# LNA.net
KiCad netlist of a schematic drawn in Altium Designer
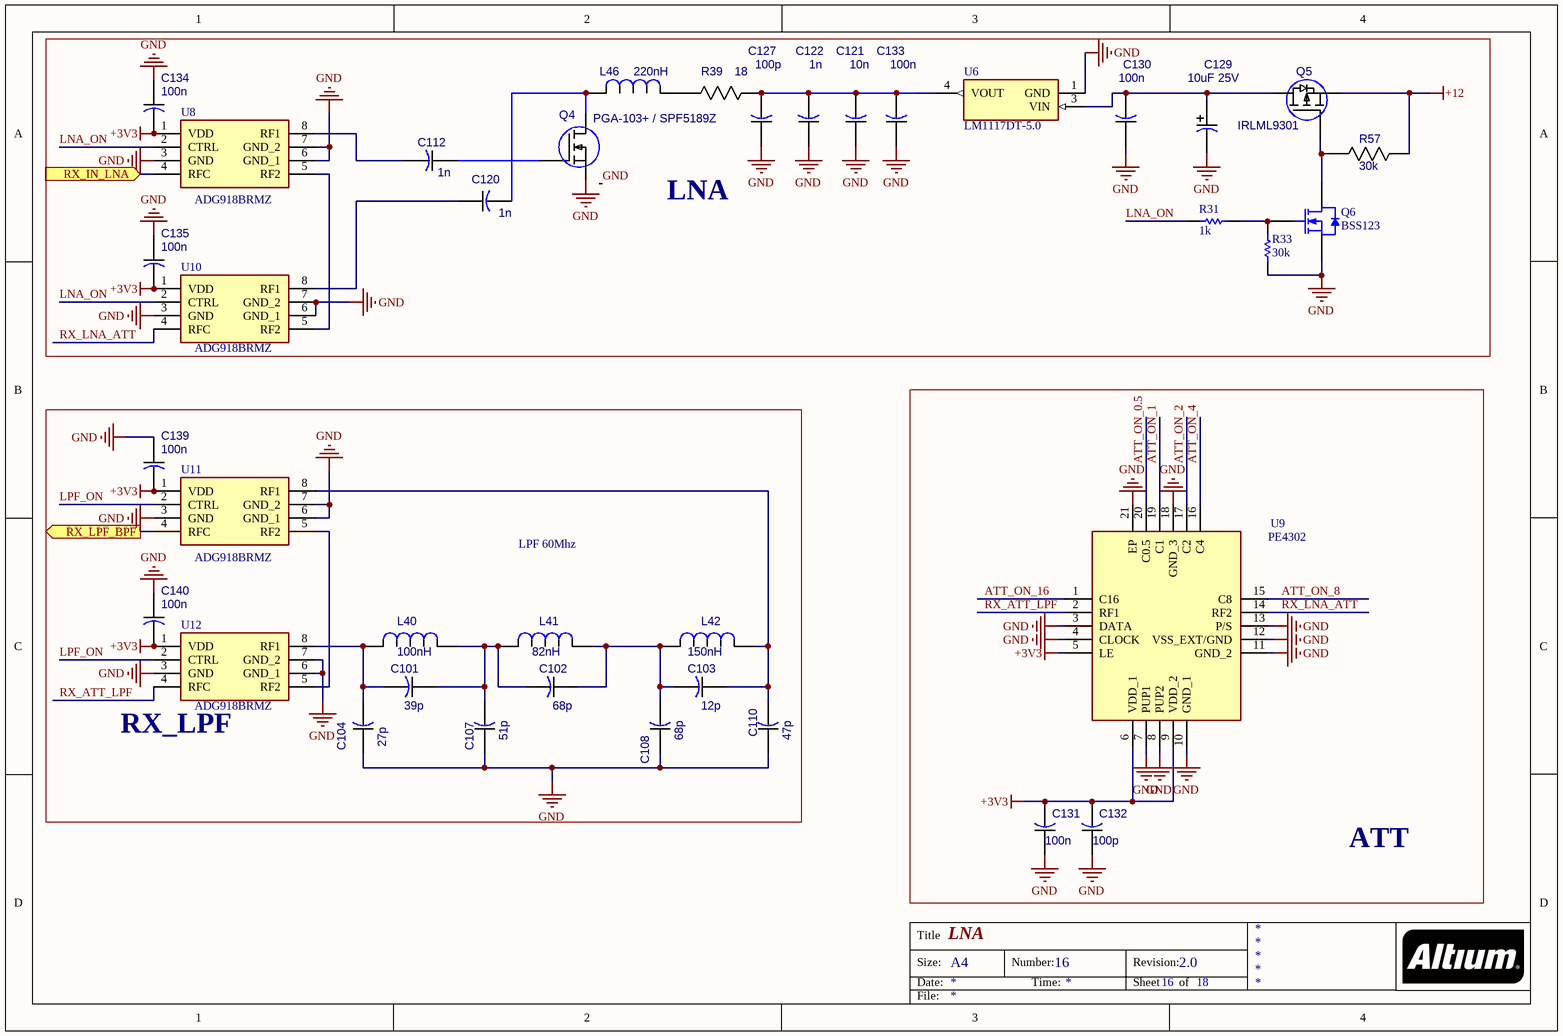
[diagram p0: LNA.SchDoc]

(export (version "E")
  (design (tool "Eeschema 10.0.6"))
  (components
    (comp (ref "C101")
      (value "39p")
      (footprint "CAP_0805")
      (description "CAP_0805")
      (libsource (lib "*") (part "CAP_0805"))
    )
    (comp (ref "C102")
      (value "68p")
      (footprint "CAP_0805")
      (description "CAP_0805")
      (libsource (lib "*") (part "CAP_0805"))
    )
    (comp (ref "C103")
      (value "12p")
      (footprint "CAP_0805")
      (description "CAP_0805")
      (libsource (lib "*") (part "CAP_0805"))
    )
    (comp (ref "C104")
      (value "27p")
      (footprint "CAP_0805")
      (description "CAP_0805")
      (libsource (lib "*") (part "CAP_0805"))
    )
    (comp (ref "C107")
      (value "51p")
      (footprint "CAP_0805")
      (description "CAP_0805")
      (libsource (lib "*") (part "CAP_0805"))
    )
    (comp (ref "C108")
      (value "68p")
      (footprint "CAP_0805")
      (description "CAP_0805")
      (libsource (lib "*") (part "CAP_0805"))
    )
    (comp (ref "C110")
      (value "47p")
      (footprint "CAP_0805")
      (description "CAP_0805")
      (libsource (lib "*") (part "CAP_0805"))
    )
    (comp (ref "C112")
      (value "1n")
      (footprint "CAP_0805")
      (description "CAP_0805")
      (libsource (lib "*") (part "CAP_0805"))
    )
    (comp (ref "C120")
      (value "1n")
      (footprint "CAP_0805")
      (description "CAP_0805")
      (libsource (lib "*") (part "CAP_0805"))
    )
    (comp (ref "C121")
      (value "10n")
      (footprint "6-0805_M")
      (description "CAP_0805")
      (libsource (lib "*") (part "CAP_0805"))
    )
    (comp (ref "C122")
      (value "1n")
      (footprint "6-0805_M")
      (description "CAP_0805")
      (libsource (lib "*") (part "CAP_0805"))
    )
    (comp (ref "C127")
      (value "100p")
      (footprint "6-0805_M")
      (description "CAP_0805")
      (libsource (lib "*") (part "CAP_0805"))
    )
    (comp (ref "C129")
      (value "10uF 25V")
      (footprint "CAPAE_5.3x5.3h6.1")
      (description "CAPAE_5.3x5.3h6.1")
      (libsource (lib "*") (part "CAPAE_5.3x5.3h6.1"))
    )
    (comp (ref "C130")
      (value "100n")
      (footprint "CAP_0805")
      (description "CAP_0805")
      (libsource (lib "") (part "CAP_0805_1"))
    )
    (comp (ref "C131")
      (value "100n")
      (footprint "6-0805_M")
      (description "CAP_0805")
      (libsource (lib "*") (part "CAP_0805"))
    )
    (comp (ref "C132")
      (value "100p")
      (footprint "6-0805_M")
      (description "CAP_0805")
      (libsource (lib "*") (part "CAP_0805"))
    )
    (comp (ref "C133")
      (value "100n")
      (footprint "CAP_0805")
      (description "CAP_0805")
      (libsource (lib "*") (part "CAP_0805"))
    )
    (comp (ref "C134")
      (value "100n")
      (footprint "CAP_0805")
      (description "CAP_0805")
      (libsource (lib "*") (part "CAP_0805"))
    )
    (comp (ref "C135")
      (value "100n")
      (footprint "CAP_0805")
      (description "CAP_0805")
      (libsource (lib "*") (part "CAP_0805"))
    )
    (comp (ref "C139")
      (value "100n")
      (footprint "CAP_0805")
      (description "CAP_0805")
      (libsource (lib "*") (part "CAP_0805"))
    )
    (comp (ref "C140")
      (value "100n")
      (footprint "CAP_0805")
      (description "CAP_0805")
      (libsource (lib "*") (part "CAP_0805"))
    )
    (comp (ref "L40")
      (value "100nH")
      (footprint "IND_0805")
      (description "IND_0805")
      (libsource (lib "*") (part "IND_0805"))
    )
    (comp (ref "L41")
      (value "82nH")
      (footprint "IND_0805")
      (description "IND_0805")
      (libsource (lib "*") (part "IND_0805"))
    )
    (comp (ref "L42")
      (value "150nH")
      (footprint "IND_0805")
      (description "IND_0805")
      (libsource (lib "*") (part "IND_0805"))
    )
    (comp (ref "L46")
      (value "220nH")
      (footprint "IND_1206")
      (description "IND_1206")
      (libsource (lib "*") (part "IND_1206"))
    )
    (comp (ref "Q4")
      (value "PGA-103+ / SPF5189Z")
      (footprint "SOT89")
      (libsource (lib "*") (part "PGA-103+"))
    )
    (comp (ref "Q5")
      (value "IRLML9301")
      (footprint "SOT23")
      (description "MOSFET")
      (libsource (lib "*") (part "MOSFET_ENH_PD"))
    )
    (comp (ref "Q6")
      (value "BSS123")
      (footprint "FAIR-SOT23-3_V")
      (fields (field (name "MANUFACTURER") "Fairchild"))
      (libsource (lib "Altium Content Vault") (part "NEMOS-GSD-3"))
    )
    (comp (ref "R31")
      (value "1k")
      (footprint "RESC2013X60X40NL20T25")
      (description "RES_0805")
      (fields (field (name "MANUFACTURER") "Panasonic") (field (name "PART NUMBER") "ERA-6AEB303V"))
      (libsource (lib "Altium Content Vault") (part "RES"))
    )
    (comp (ref "R33")
      (value "30k")
      (footprint "RESC2013X60X40NL20T25")
      (description "RES_0805")
      (fields (field (name "MANUFACTURER") "Panasonic") (field (name "PART NUMBER") "ERA-6AEB303V"))
      (libsource (lib "Altium Content Vault") (part "RES"))
    )
    (comp (ref "R39")
      (value "18")
      (footprint "RES_1206")
      (description "RES_1206")
      (libsource (lib "*") (part "RES_1206"))
    )
    (comp (ref "R57")
      (value "30k")
      (footprint "RES_0805")
      (description "RES_0805")
      (libsource (lib "*") (part "RES_0805"))
    )
    (comp (ref "U6")
      (value "LM1117DT-5.0")
      (footprint "SamacSys:TO228P991X238-3N")
      (description "Integrated Circuit")
      (fields
        (field (name "MANUFACTURER_PART_NUMBER") "LM1117DT-ADJ")
        (field (name "MOUSER PART NUMBER") "926-LM1117DT-ADJ")
      )
      (libsource (lib "*") (part "LM1117DT-ADJ"))
    )
    (comp (ref "U8")
      (value "ADG918BRMZ")
      (footprint "SamacSys:SOP65P490X110-8N")
      (description "Integrated Circuit")
      (fields (field (name "MOUSER PART NUMBER") "584-ADG918BRMZ") (field (name "RS PART NUMBER") "4969212P"))
      (libsource (lib "*") (part "ADG918BRMZ"))
    )
    (comp (ref "U9")
      (value "PE4302")
      (footprint "SamacSys:QFN50P400X400X90-21N")
      (description "Integrated Circuit")
      (fields (field (name "MANUFACTURER_PART_NUMBER") "PE4312C-Z"))
      (libsource (lib "*") (part "PE4312C-Z"))
    )
    (comp (ref "U10")
      (value "ADG918BRMZ")
      (footprint "SamacSys:SOP65P490X110-8N")
      (description "Integrated Circuit")
      (fields (field (name "MOUSER PART NUMBER") "584-ADG918BRMZ") (field (name "RS PART NUMBER") "4969212P"))
      (libsource (lib "*") (part "ADG918BRMZ"))
    )
    (comp (ref "U11")
      (value "ADG918BRMZ")
      (footprint "SamacSys:SOP65P490X110-8N")
      (description "Integrated Circuit")
      (fields (field (name "MOUSER PART NUMBER") "584-ADG918BRMZ") (field (name "RS PART NUMBER") "4969212P"))
      (libsource (lib "*") (part "ADG918BRMZ"))
    )
    (comp (ref "U12")
      (value "ADG918BRMZ")
      (footprint "SamacSys:SOP65P490X110-8N")
      (description "Integrated Circuit")
      (fields (field (name "MOUSER PART NUMBER") "584-ADG918BRMZ") (field (name "RS PART NUMBER") "4969212P"))
      (libsource (lib "*") (part "ADG918BRMZ"))
    )
  )
  (nets
    (net (code "1") (name "+3V3") (class "Default")
      (node (ref "C131") (pin "2") (pinfunction "2_2") (pintype "passive"))
      (node (ref "C132") (pin "2") (pinfunction "2_2") (pintype "passive"))
      (node (ref "C134") (pin "2") (pinfunction "2_2") (pintype "passive"))
      (node (ref "C135") (pin "2") (pinfunction "2_2") (pintype "passive"))
      (node (ref "C139") (pin "2") (pinfunction "2_2") (pintype "passive"))
      (node (ref "C140") (pin "2") (pinfunction "2_2") (pintype "passive"))
      (node (ref "U10") (pin "1") (pinfunction "VDD_1") (pintype "power_in"))
      (node (ref "U11") (pin "1") (pinfunction "VDD_1") (pintype "power_in"))
      (node (ref "U12") (pin "1") (pinfunction "VDD_1") (pintype "power_in"))
      (node (ref "U8") (pin "1") (pinfunction "VDD_1") (pintype "power_in"))
      (node (ref "U9") (pin "5") (pinfunction "LE_5") (pintype "passive"))
      (node (ref "U9") (pin "6") (pinfunction "VDD_1_6") (pintype "passive"))
      (node (ref "U9") (pin "9") (pinfunction "VDD_2_9") (pintype "passive"))
    )
    (net (code "2") (name "+12") (class "Default")
      (node (ref "Q5") (pin "2") (pinfunction "S_2") (pintype "passive"))
      (node (ref "R57") (pin "2") (pinfunction "2_2") (pintype "passive"))
    )
    (net (code "3") (name "/ATT_ON_0.5") (class "Default")
      (node (ref "U9") (pin "20") (pinfunction "C0.5_20") (pintype "passive"))
    )
    (net (code "4") (name "/ATT_ON_1") (class "Default")
      (node (ref "U9") (pin "19") (pinfunction "C1_19") (pintype "passive"))
    )
    (net (code "5") (name "/ATT_ON_2") (class "Default")
      (node (ref "U9") (pin "17") (pinfunction "C2_17") (pintype "passive"))
    )
    (net (code "6") (name "/ATT_ON_4") (class "Default")
      (node (ref "U9") (pin "16") (pinfunction "C4_16") (pintype "passive"))
    )
    (net (code "7") (name "/ATT_ON_8") (class "Default")
      (node (ref "U9") (pin "15") (pinfunction "C8_15") (pintype "passive"))
    )
    (net (code "8") (name "/ATT_ON_16") (class "Default")
      (node (ref "U9") (pin "1") (pinfunction "C16_1") (pintype "passive"))
    )
    (net (code "9") (name "/LNA_ON") (class "Default")
      (node (ref "R31") (pin "2") (pinfunction "2_2") (pintype "passive"))
      (node (ref "U10") (pin "2") (pinfunction "CTRL_2") (pintype "passive"))
      (node (ref "U8") (pin "2") (pinfunction "CTRL_2") (pintype "passive"))
    )
    (net (code "10") (name "/LPF_ON") (class "Default")
      (node (ref "U11") (pin "2") (pinfunction "CTRL_2") (pintype "passive"))
      (node (ref "U12") (pin "2") (pinfunction "CTRL_2") (pintype "passive"))
    )
    (net (code "11") (name "/RX_ATT_LPF") (class "Default")
      (node (ref "U12") (pin "4") (pinfunction "RFC_4") (pintype "passive"))
      (node (ref "U9") (pin "2") (pinfunction "RF1_2") (pintype "passive"))
    )
    (net (code "12") (name "/RX_IN_LNA") (class "Default")
      (node (ref "U8") (pin "4") (pinfunction "RFC_4") (pintype "passive"))
    )
    (net (code "13") (name "/RX_LNA_ATT") (class "Default")
      (node (ref "U10") (pin "4") (pinfunction "RFC_4") (pintype "passive"))
      (node (ref "U9") (pin "14") (pinfunction "RF2_14") (pintype "passive"))
    )
    (net (code "14") (name "/RX_LPF_BPF") (class "Default")
      (node (ref "U11") (pin "4") (pinfunction "RFC_4") (pintype "passive"))
    )
    (net (code "15") (name "GND") (class "Default")
      (node (ref "C104") (pin "1") (pinfunction "1_1") (pintype "passive"))
      (node (ref "C107") (pin "1") (pinfunction "1_1") (pintype "passive"))
      (node (ref "C108") (pin "1") (pinfunction "1_1") (pintype "passive"))
      (node (ref "C110") (pin "1") (pinfunction "1_1") (pintype "passive"))
      (node (ref "C121") (pin "1") (pinfunction "1_1") (pintype "passive"))
      (node (ref "C122") (pin "1") (pinfunction "1_1") (pintype "passive"))
      (node (ref "C127") (pin "1") (pinfunction "1_1") (pintype "passive"))
      (node (ref "C129") (pin "2") (pinfunction "MINUS_2") (pintype "passive"))
      (node (ref "C130") (pin "1") (pinfunction "1_1") (pintype "passive"))
      (node (ref "C131") (pin "1") (pinfunction "1_1") (pintype "passive"))
      (node (ref "C132") (pin "1") (pinfunction "1_1") (pintype "passive"))
      (node (ref "C133") (pin "1") (pinfunction "1_1") (pintype "passive"))
      (node (ref "C134") (pin "1") (pinfunction "1_1") (pintype "passive"))
      (node (ref "C135") (pin "1") (pinfunction "1_1") (pintype "passive"))
      (node (ref "C139") (pin "1") (pinfunction "1_1") (pintype "passive"))
      (node (ref "C140") (pin "1") (pinfunction "1_1") (pintype "passive"))
      (node (ref "Q4") (pin "0") (pinfunction "0_0") (pintype "passive"))
      (node (ref "Q4") (pin "2") (pinfunction "S_2") (pintype "passive"))
      (node (ref "Q6") (pin "2") (pinfunction "S_2") (pintype "passive"))
      (node (ref "R33") (pin "1") (pinfunction "1_1") (pintype "passive"))
      (node (ref "U10") (pin "3") (pinfunction "GND_3") (pintype "power_in"))
      (node (ref "U10") (pin "6") (pinfunction "GND_1_6") (pintype "power_in"))
      (node (ref "U10") (pin "7") (pinfunction "GND_2_7") (pintype "power_in"))
      (node (ref "U11") (pin "3") (pinfunction "GND_3") (pintype "power_in"))
      (node (ref "U11") (pin "6") (pinfunction "GND_1_6") (pintype "power_in"))
      (node (ref "U11") (pin "7") (pinfunction "GND_2_7") (pintype "power_in"))
      (node (ref "U12") (pin "3") (pinfunction "GND_3") (pintype "power_in"))
      (node (ref "U12") (pin "6") (pinfunction "GND_1_6") (pintype "power_in"))
      (node (ref "U12") (pin "7") (pinfunction "GND_2_7") (pintype "power_in"))
      (node (ref "U6") (pin "1") (pinfunction "GND_1") (pintype "passive"))
      (node (ref "U8") (pin "3") (pinfunction "GND_3") (pintype "power_in"))
      (node (ref "U8") (pin "6") (pinfunction "GND_1_6") (pintype "power_in"))
      (node (ref "U8") (pin "7") (pinfunction "GND_2_7") (pintype "power_in"))
      (node (ref "U9") (pin "10") (pinfunction "GND_1_10") (pintype "passive"))
      (node (ref "U9") (pin "11") (pinfunction "GND_2_11") (pintype "passive"))
      (node (ref "U9") (pin "12") (pinfunction "VSS_EXT/GND_12") (pintype "passive"))
      (node (ref "U9") (pin "13") (pinfunction "P/S_13") (pintype "passive"))
      (node (ref "U9") (pin "18") (pinfunction "GND_3_18") (pintype "passive"))
      (node (ref "U9") (pin "21") (pinfunction "EP_21") (pintype "passive"))
      (node (ref "U9") (pin "3") (pinfunction "DATA_3") (pintype "passive"))
      (node (ref "U9") (pin "4") (pinfunction "CLOCK_4") (pintype "passive"))
      (node (ref "U9") (pin "7") (pinfunction "PUP1_7") (pintype "passive"))
      (node (ref "U9") (pin "8") (pinfunction "PUP2_8") (pintype "passive"))
    )
    (net (code "16") (name "Net-(C101-Pad1)") (class "Default")
      (node (ref "C101") (pin "1") (pinfunction "1_1") (pintype "passive"))
      (node (ref "C102") (pin "2") (pinfunction "2_2") (pintype "passive"))
      (node (ref "C107") (pin "2") (pinfunction "2_2") (pintype "passive"))
      (node (ref "L40") (pin "2") (pinfunction "2_2") (pintype "passive"))
      (node (ref "L41") (pin "1") (pinfunction "1_1") (pintype "passive"))
    )
    (net (code "17") (name "Net-(C102-Pad1)") (class "Default")
      (node (ref "C102") (pin "1") (pinfunction "1_1") (pintype "passive"))
      (node (ref "C103") (pin "2") (pinfunction "2_2") (pintype "passive"))
      (node (ref "C108") (pin "2") (pinfunction "2_2") (pintype "passive"))
      (node (ref "L41") (pin "2") (pinfunction "2_2") (pintype "passive"))
      (node (ref "L42") (pin "1") (pinfunction "1_1") (pintype "passive"))
    )
    (net (code "18") (name "Net-(C129-PLUS)") (class "Default")
      (node (ref "C129") (pin "1") (pinfunction "PLUS_1") (pintype "passive"))
      (node (ref "C130") (pin "2") (pinfunction "2_2") (pintype "passive"))
      (node (ref "Q5") (pin "3") (pinfunction "D_3") (pintype "passive"))
      (node (ref "U6") (pin "3") (pinfunction "VIN_3") (pintype "input"))
    )
    (net (code "19") (name "Net-(L46-1)") (class "Default")
      (node (ref "C120") (pin "2") (pinfunction "2_2") (pintype "passive"))
      (node (ref "L46") (pin "2") (pinfunction "1_2") (pintype "passive"))
      (node (ref "Q4") (pin "3") (pinfunction "D_3") (pintype "passive"))
    )
    (net (code "20") (name "Net-(L46-2)") (class "Default")
      (node (ref "L46") (pin "1") (pinfunction "2_1") (pintype "passive"))
      (node (ref "R39") (pin "2") (pinfunction "2_2") (pintype "passive"))
    )
    (net (code "21") (name "Net-(Q4-G)") (class "Default")
      (node (ref "C112") (pin "1") (pinfunction "1_1") (pintype "passive"))
      (node (ref "Q4") (pin "1") (pinfunction "G_1") (pintype "passive"))
    )
    (net (code "22") (name "Net-(Q5-G)") (class "Default")
      (node (ref "Q5") (pin "1") (pinfunction "G_1") (pintype "passive"))
      (node (ref "Q6") (pin "3") (pinfunction "D_3") (pintype "passive"))
      (node (ref "R57") (pin "1") (pinfunction "1_1") (pintype "passive"))
    )
    (net (code "23") (name "Net-(Q6-G)") (class "Default")
      (node (ref "Q6") (pin "1") (pinfunction "G_1") (pintype "passive"))
      (node (ref "R31") (pin "1") (pinfunction "1_1") (pintype "passive"))
      (node (ref "R33") (pin "2") (pinfunction "2_2") (pintype "passive"))
    )
    (net (code "24") (name "Net-(U6-VOUT)") (class "Default")
      (node (ref "C121") (pin "2") (pinfunction "2_2") (pintype "passive"))
      (node (ref "C122") (pin "2") (pinfunction "2_2") (pintype "passive"))
      (node (ref "C127") (pin "2") (pinfunction "2_2") (pintype "passive"))
      (node (ref "C133") (pin "2") (pinfunction "2_2") (pintype "passive"))
      (node (ref "R39") (pin "1") (pinfunction "1_1") (pintype "passive"))
      (node (ref "U6") (pin "4") (pinfunction "VOUT_4") (pintype "output"))
    )
    (net (code "25") (name "Net-(U8-RF1)") (class "Default")
      (node (ref "C112") (pin "2") (pinfunction "2_2") (pintype "passive"))
      (node (ref "U8") (pin "8") (pinfunction "RF1_8") (pintype "passive"))
    )
    (net (code "26") (name "Net-(U10-RF1)") (class "Default")
      (node (ref "C120") (pin "1") (pinfunction "1_1") (pintype "passive"))
      (node (ref "U10") (pin "8") (pinfunction "RF1_8") (pintype "passive"))
    )
    (net (code "27") (name "Net-(U10-RF2)") (class "Default")
      (node (ref "U10") (pin "5") (pinfunction "RF2_5") (pintype "passive"))
      (node (ref "U8") (pin "5") (pinfunction "RF2_5") (pintype "passive"))
    )
    (net (code "28") (name "Net-(U11-RF1)") (class "Default")
      (node (ref "C103") (pin "1") (pinfunction "1_1") (pintype "passive"))
      (node (ref "C110") (pin "2") (pinfunction "2_2") (pintype "passive"))
      (node (ref "L42") (pin "2") (pinfunction "2_2") (pintype "passive"))
      (node (ref "U11") (pin "8") (pinfunction "RF1_8") (pintype "passive"))
    )
    (net (code "29") (name "Net-(U11-RF2)") (class "Default")
      (node (ref "U11") (pin "5") (pinfunction "RF2_5") (pintype "passive"))
      (node (ref "U12") (pin "5") (pinfunction "RF2_5") (pintype "passive"))
    )
    (net (code "30") (name "Net-(U12-RF1)") (class "Default")
      (node (ref "C101") (pin "2") (pinfunction "2_2") (pintype "passive"))
      (node (ref "C104") (pin "2") (pinfunction "2_2") (pintype "passive"))
      (node (ref "L40") (pin "1") (pinfunction "1_1") (pintype "passive"))
      (node (ref "U12") (pin "8") (pinfunction "RF1_8") (pintype "passive"))
    )
  )
)
